# 02BA_-_Pressure.net
KiCad netlist of a schematic drawn in EAGLE
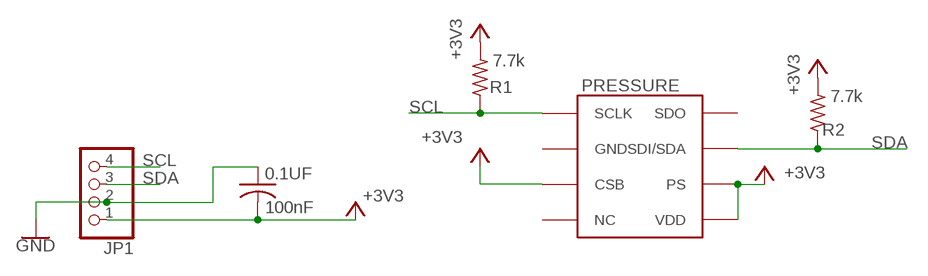
[diagram p0: schematic, sheet 1]

(export (version "E")
  (design (tool "Eeschema 10.0.6"))
  (components
    (comp (ref "0.1UF")
      (value "100nF")
      (footprint "eagle-import:C0805")
      (libsource (lib "eagle-import") (part "C-USC0805"))
    )
    (comp (ref "JP1")
      (value "PINHD-1X4")
      (footprint "eagle-import:1X04")
      (libsource (lib "eagle-import") (part "PINHD-1X4"))
    )
    (comp (ref "PRESSURE")
      (value "MS5803-01BA")
      (footprint "eagle-import:SMD")
      (libsource (lib "eagle-import") (part "MS5803-01BA"))
    )
    (comp (ref "R1")
      (value "7.7k")
      (footprint "eagle-import:R0805")
      (libsource (lib "eagle-import") (part "R-US_R0805"))
    )
    (comp (ref "R2")
      (value "7.7k")
      (footprint "eagle-import:R0805")
      (libsource (lib "eagle-import") (part "R-US_R0805"))
    )
  )
  (nets
    (net (code "1") (name "+3V3") (class "Default")
      (node (ref "0.1UF") (pin "2") (pinfunction "2_2") (pintype "passive"))
      (node (ref "JP1") (pin "1") (pinfunction "1_1") (pintype "passive"))
      (node (ref "PRESSURE") (pin "CSB") (pinfunction "CSB_CSB") (pintype "bidirectional"))
      (node (ref "PRESSURE") (pin "PS") (pinfunction "PS_PS") (pintype "bidirectional"))
      (node (ref "PRESSURE") (pin "VDD") (pinfunction "VDD_VDD") (pintype "bidirectional"))
      (node (ref "R1") (pin "2") (pinfunction "2_2") (pintype "passive"))
      (node (ref "R2") (pin "2") (pinfunction "2_2") (pintype "passive"))
    )
    (net (code "2") (name "/SCL") (class "Default")
      (node (ref "JP1") (pin "4") (pinfunction "4_4") (pintype "passive"))
      (node (ref "PRESSURE") (pin "SCLK") (pinfunction "SCLK_SCLK") (pintype "bidirectional"))
      (node (ref "R1") (pin "1") (pinfunction "1_1") (pintype "passive"))
    )
    (net (code "3") (name "/SDA") (class "Default")
      (node (ref "JP1") (pin "3") (pinfunction "3_3") (pintype "passive"))
      (node (ref "PRESSURE") (pin "SDI/SDA") (pinfunction "SDI/SDA_SDI/SDA") (pintype "bidirectional"))
      (node (ref "R2") (pin "1") (pinfunction "1_1") (pintype "passive"))
    )
    (net (code "4") (name "GND") (class "Default")
      (node (ref "0.1UF") (pin "1") (pinfunction "1_1") (pintype "passive"))
      (node (ref "JP1") (pin "2") (pinfunction "2_2") (pintype "passive"))
    )
    (net (code "5") (name "unconnected-(PRESSURE-PadGND)") (class "Default")
      (node (ref "PRESSURE") (pin "GND") (pinfunction "GND_GND") (pintype "bidirectional"))
    )
    (net (code "6") (name "unconnected-(PRESSURE-PadNC)") (class "Default")
      (node (ref "PRESSURE") (pin "NC") (pinfunction "NC_NC") (pintype "bidirectional"))
    )
    (net (code "7") (name "unconnected-(PRESSURE-PadSDO)") (class "Default")
      (node (ref "PRESSURE") (pin "SDO") (pinfunction "SDO_SDO") (pintype "bidirectional"))
    )
  )
)
